# bus.net
KiCad netlist of a schematic drawn in EAGLE
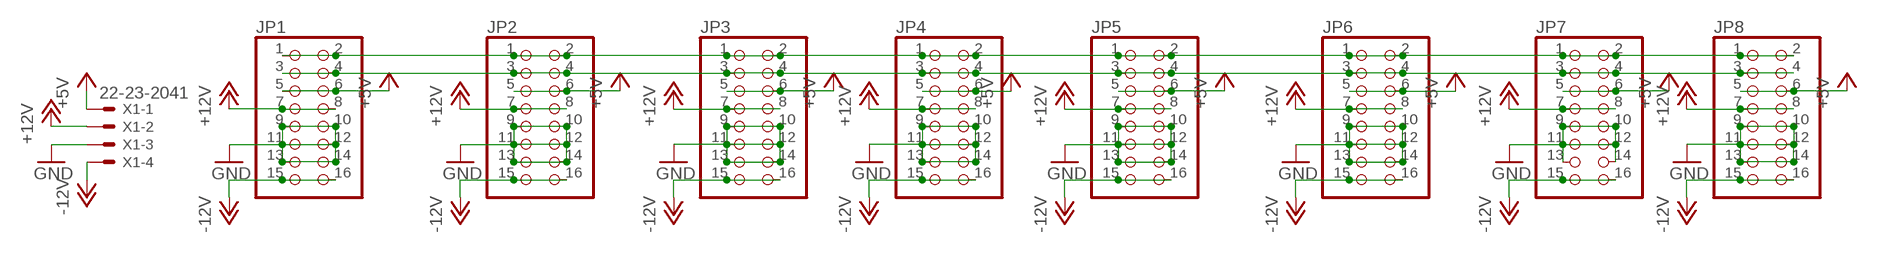
[diagram p0: schematic, sheet 1]

(export (version "E")
  (design (tool "Eeschema 10.0.6"))
  (components
    (comp (ref "JP1")
      (value "PINHD-2X8")
      (footprint "eagle-import:2X08")
      (libsource (lib "eagle-import") (part "PINHD-2X8"))
    )
    (comp (ref "JP2")
      (value "PINHD-2X8")
      (footprint "eagle-import:2X08")
      (libsource (lib "eagle-import") (part "PINHD-2X8"))
    )
    (comp (ref "JP3")
      (value "PINHD-2X8")
      (footprint "eagle-import:2X08")
      (libsource (lib "eagle-import") (part "PINHD-2X8"))
    )
    (comp (ref "JP4")
      (value "PINHD-2X8")
      (footprint "eagle-import:2X08")
      (libsource (lib "eagle-import") (part "PINHD-2X8"))
    )
    (comp (ref "JP5")
      (value "PINHD-2X8")
      (footprint "eagle-import:2X08")
      (libsource (lib "eagle-import") (part "PINHD-2X8"))
    )
    (comp (ref "JP6")
      (value "PINHD-2X8")
      (footprint "eagle-import:2X08")
      (libsource (lib "eagle-import") (part "PINHD-2X8"))
    )
    (comp (ref "JP7")
      (value "PINHD-2X8")
      (footprint "eagle-import:2X08")
      (libsource (lib "eagle-import") (part "PINHD-2X8"))
    )
    (comp (ref "JP8")
      (value "PINHD-2X8")
      (footprint "eagle-import:2X08")
      (libsource (lib "eagle-import") (part "PINHD-2X8"))
    )
    (comp (ref "X1")
      (value "22-23-2041")
      (footprint "eagle-import:22-23-2041")
      (fields (field (name "MF") "MOLEX"))
      (libsource (lib "eagle-import") (part "22-23-2041"))
    )
  )
  (nets
    (net (code "1") (name "+5V") (class "Default")
      (node (ref "JP1") (pin "5") (pinfunction "5_5") (pintype "passive"))
      (node (ref "JP1") (pin "6") (pinfunction "6_6") (pintype "passive"))
      (node (ref "JP2") (pin "5") (pinfunction "5_5") (pintype "passive"))
      (node (ref "JP2") (pin "6") (pinfunction "6_6") (pintype "passive"))
      (node (ref "JP3") (pin "5") (pinfunction "5_5") (pintype "passive"))
      (node (ref "JP3") (pin "6") (pinfunction "6_6") (pintype "passive"))
      (node (ref "JP4") (pin "5") (pinfunction "5_5") (pintype "passive"))
      (node (ref "JP4") (pin "6") (pinfunction "6_6") (pintype "passive"))
      (node (ref "JP5") (pin "5") (pinfunction "5_5") (pintype "passive"))
      (node (ref "JP5") (pin "6") (pinfunction "6_6") (pintype "passive"))
      (node (ref "JP6") (pin "5") (pinfunction "5_5") (pintype "passive"))
      (node (ref "JP6") (pin "6") (pinfunction "6_6") (pintype "passive"))
      (node (ref "JP7") (pin "5") (pinfunction "5_5") (pintype "passive"))
      (node (ref "JP7") (pin "6") (pinfunction "6_6") (pintype "passive"))
      (node (ref "JP8") (pin "5") (pinfunction "5_5") (pintype "passive"))
      (node (ref "JP8") (pin "6") (pinfunction "6_6") (pintype "passive"))
      (node (ref "X1") (pin "1") (pinfunction "S_1") (pintype "passive"))
    )
    (net (code "2") (name "+12V") (class "Default")
      (node (ref "JP1") (pin "7") (pinfunction "7_7") (pintype "passive"))
      (node (ref "JP1") (pin "8") (pinfunction "8_8") (pintype "passive"))
      (node (ref "JP2") (pin "7") (pinfunction "7_7") (pintype "passive"))
      (node (ref "JP2") (pin "8") (pinfunction "8_8") (pintype "passive"))
      (node (ref "JP3") (pin "7") (pinfunction "7_7") (pintype "passive"))
      (node (ref "JP3") (pin "8") (pinfunction "8_8") (pintype "passive"))
      (node (ref "JP4") (pin "7") (pinfunction "7_7") (pintype "passive"))
      (node (ref "JP4") (pin "8") (pinfunction "8_8") (pintype "passive"))
      (node (ref "JP5") (pin "7") (pinfunction "7_7") (pintype "passive"))
      (node (ref "JP5") (pin "8") (pinfunction "8_8") (pintype "passive"))
      (node (ref "JP6") (pin "7") (pinfunction "7_7") (pintype "passive"))
      (node (ref "JP6") (pin "8") (pinfunction "8_8") (pintype "passive"))
      (node (ref "JP7") (pin "7") (pinfunction "7_7") (pintype "passive"))
      (node (ref "JP7") (pin "8") (pinfunction "8_8") (pintype "passive"))
      (node (ref "JP8") (pin "7") (pinfunction "7_7") (pintype "passive"))
      (node (ref "JP8") (pin "8") (pinfunction "8_8") (pintype "passive"))
      (node (ref "X1") (pin "2") (pinfunction "S_2") (pintype "passive"))
    )
    (net (code "3") (name "-12V") (class "Default")
      (node (ref "JP1") (pin "15") (pinfunction "15_15") (pintype "passive"))
      (node (ref "JP1") (pin "16") (pinfunction "16_16") (pintype "passive"))
      (node (ref "JP2") (pin "15") (pinfunction "15_15") (pintype "passive"))
      (node (ref "JP2") (pin "16") (pinfunction "16_16") (pintype "passive"))
      (node (ref "JP3") (pin "15") (pinfunction "15_15") (pintype "passive"))
      (node (ref "JP3") (pin "16") (pinfunction "16_16") (pintype "passive"))
      (node (ref "JP4") (pin "15") (pinfunction "15_15") (pintype "passive"))
      (node (ref "JP4") (pin "16") (pinfunction "16_16") (pintype "passive"))
      (node (ref "JP5") (pin "15") (pinfunction "15_15") (pintype "passive"))
      (node (ref "JP5") (pin "16") (pinfunction "16_16") (pintype "passive"))
      (node (ref "JP6") (pin "15") (pinfunction "15_15") (pintype "passive"))
      (node (ref "JP6") (pin "16") (pinfunction "16_16") (pintype "passive"))
      (node (ref "JP7") (pin "15") (pinfunction "15_15") (pintype "passive"))
      (node (ref "JP7") (pin "16") (pinfunction "16_16") (pintype "passive"))
      (node (ref "JP8") (pin "15") (pinfunction "15_15") (pintype "passive"))
      (node (ref "JP8") (pin "16") (pinfunction "16_16") (pintype "passive"))
      (node (ref "X1") (pin "4") (pinfunction "S_4") (pintype "passive"))
    )
    (net (code "4") (name "GND") (class "Default")
      (node (ref "JP1") (pin "10") (pinfunction "10_10") (pintype "passive"))
      (node (ref "JP1") (pin "11") (pinfunction "11_11") (pintype "passive"))
      (node (ref "JP1") (pin "12") (pinfunction "12_12") (pintype "passive"))
      (node (ref "JP1") (pin "13") (pinfunction "13_13") (pintype "passive"))
      (node (ref "JP1") (pin "14") (pinfunction "14_14") (pintype "passive"))
      (node (ref "JP1") (pin "9") (pinfunction "9_9") (pintype "passive"))
      (node (ref "JP2") (pin "10") (pinfunction "10_10") (pintype "passive"))
      (node (ref "JP2") (pin "11") (pinfunction "11_11") (pintype "passive"))
      (node (ref "JP2") (pin "12") (pinfunction "12_12") (pintype "passive"))
      (node (ref "JP2") (pin "13") (pinfunction "13_13") (pintype "passive"))
      (node (ref "JP2") (pin "14") (pinfunction "14_14") (pintype "passive"))
      (node (ref "JP2") (pin "9") (pinfunction "9_9") (pintype "passive"))
      (node (ref "JP3") (pin "10") (pinfunction "10_10") (pintype "passive"))
      (node (ref "JP3") (pin "11") (pinfunction "11_11") (pintype "passive"))
      (node (ref "JP3") (pin "12") (pinfunction "12_12") (pintype "passive"))
      (node (ref "JP3") (pin "13") (pinfunction "13_13") (pintype "passive"))
      (node (ref "JP3") (pin "14") (pinfunction "14_14") (pintype "passive"))
      (node (ref "JP3") (pin "9") (pinfunction "9_9") (pintype "passive"))
      (node (ref "JP4") (pin "10") (pinfunction "10_10") (pintype "passive"))
      (node (ref "JP4") (pin "11") (pinfunction "11_11") (pintype "passive"))
      (node (ref "JP4") (pin "12") (pinfunction "12_12") (pintype "passive"))
      (node (ref "JP4") (pin "13") (pinfunction "13_13") (pintype "passive"))
      (node (ref "JP4") (pin "14") (pinfunction "14_14") (pintype "passive"))
      (node (ref "JP4") (pin "9") (pinfunction "9_9") (pintype "passive"))
      (node (ref "JP5") (pin "10") (pinfunction "10_10") (pintype "passive"))
      (node (ref "JP5") (pin "11") (pinfunction "11_11") (pintype "passive"))
      (node (ref "JP5") (pin "12") (pinfunction "12_12") (pintype "passive"))
      (node (ref "JP5") (pin "13") (pinfunction "13_13") (pintype "passive"))
      (node (ref "JP5") (pin "14") (pinfunction "14_14") (pintype "passive"))
      (node (ref "JP5") (pin "9") (pinfunction "9_9") (pintype "passive"))
      (node (ref "JP6") (pin "10") (pinfunction "10_10") (pintype "passive"))
      (node (ref "JP6") (pin "11") (pinfunction "11_11") (pintype "passive"))
      (node (ref "JP6") (pin "12") (pinfunction "12_12") (pintype "passive"))
      (node (ref "JP6") (pin "13") (pinfunction "13_13") (pintype "passive"))
      (node (ref "JP6") (pin "14") (pinfunction "14_14") (pintype "passive"))
      (node (ref "JP6") (pin "9") (pinfunction "9_9") (pintype "passive"))
      (node (ref "JP7") (pin "10") (pinfunction "10_10") (pintype "passive"))
      (node (ref "JP7") (pin "11") (pinfunction "11_11") (pintype "passive"))
      (node (ref "JP7") (pin "12") (pinfunction "12_12") (pintype "passive"))
      (node (ref "JP7") (pin "13") (pinfunction "13_13") (pintype "passive"))
      (node (ref "JP7") (pin "14") (pinfunction "14_14") (pintype "passive"))
      (node (ref "JP7") (pin "9") (pinfunction "9_9") (pintype "passive"))
      (node (ref "JP8") (pin "10") (pinfunction "10_10") (pintype "passive"))
      (node (ref "JP8") (pin "11") (pinfunction "11_11") (pintype "passive"))
      (node (ref "JP8") (pin "12") (pinfunction "12_12") (pintype "passive"))
      (node (ref "JP8") (pin "13") (pinfunction "13_13") (pintype "passive"))
      (node (ref "JP8") (pin "14") (pinfunction "14_14") (pintype "passive"))
      (node (ref "JP8") (pin "9") (pinfunction "9_9") (pintype "passive"))
      (node (ref "X1") (pin "3") (pinfunction "S_3") (pintype "passive"))
    )
    (net (code "5") (name "Net-(JP1-Pad1)") (class "Default")
      (node (ref "JP1") (pin "1") (pinfunction "1_1") (pintype "passive"))
      (node (ref "JP1") (pin "2") (pinfunction "2_2") (pintype "passive"))
      (node (ref "JP2") (pin "1") (pinfunction "1_1") (pintype "passive"))
      (node (ref "JP2") (pin "2") (pinfunction "2_2") (pintype "passive"))
      (node (ref "JP3") (pin "1") (pinfunction "1_1") (pintype "passive"))
      (node (ref "JP3") (pin "2") (pinfunction "2_2") (pintype "passive"))
      (node (ref "JP4") (pin "1") (pinfunction "1_1") (pintype "passive"))
      (node (ref "JP4") (pin "2") (pinfunction "2_2") (pintype "passive"))
      (node (ref "JP5") (pin "1") (pinfunction "1_1") (pintype "passive"))
      (node (ref "JP5") (pin "2") (pinfunction "2_2") (pintype "passive"))
      (node (ref "JP6") (pin "1") (pinfunction "1_1") (pintype "passive"))
      (node (ref "JP6") (pin "2") (pinfunction "2_2") (pintype "passive"))
      (node (ref "JP7") (pin "1") (pinfunction "1_1") (pintype "passive"))
      (node (ref "JP7") (pin "2") (pinfunction "2_2") (pintype "passive"))
      (node (ref "JP8") (pin "1") (pinfunction "1_1") (pintype "passive"))
      (node (ref "JP8") (pin "2") (pinfunction "2_2") (pintype "passive"))
    )
    (net (code "6") (name "Net-(JP1-Pad3)") (class "Default")
      (node (ref "JP1") (pin "3") (pinfunction "3_3") (pintype "passive"))
      (node (ref "JP1") (pin "4") (pinfunction "4_4") (pintype "passive"))
      (node (ref "JP2") (pin "3") (pinfunction "3_3") (pintype "passive"))
      (node (ref "JP2") (pin "4") (pinfunction "4_4") (pintype "passive"))
      (node (ref "JP3") (pin "3") (pinfunction "3_3") (pintype "passive"))
      (node (ref "JP3") (pin "4") (pinfunction "4_4") (pintype "passive"))
      (node (ref "JP4") (pin "3") (pinfunction "3_3") (pintype "passive"))
      (node (ref "JP4") (pin "4") (pinfunction "4_4") (pintype "passive"))
      (node (ref "JP5") (pin "3") (pinfunction "3_3") (pintype "passive"))
      (node (ref "JP5") (pin "4") (pinfunction "4_4") (pintype "passive"))
      (node (ref "JP6") (pin "3") (pinfunction "3_3") (pintype "passive"))
      (node (ref "JP6") (pin "4") (pinfunction "4_4") (pintype "passive"))
      (node (ref "JP7") (pin "3") (pinfunction "3_3") (pintype "passive"))
      (node (ref "JP7") (pin "4") (pinfunction "4_4") (pintype "passive"))
      (node (ref "JP8") (pin "3") (pinfunction "3_3") (pintype "passive"))
      (node (ref "JP8") (pin "4") (pinfunction "4_4") (pintype "passive"))
    )
  )
)
